# AVR_PCB.net
KiCad netlist of a schematic drawn in Altium Designer
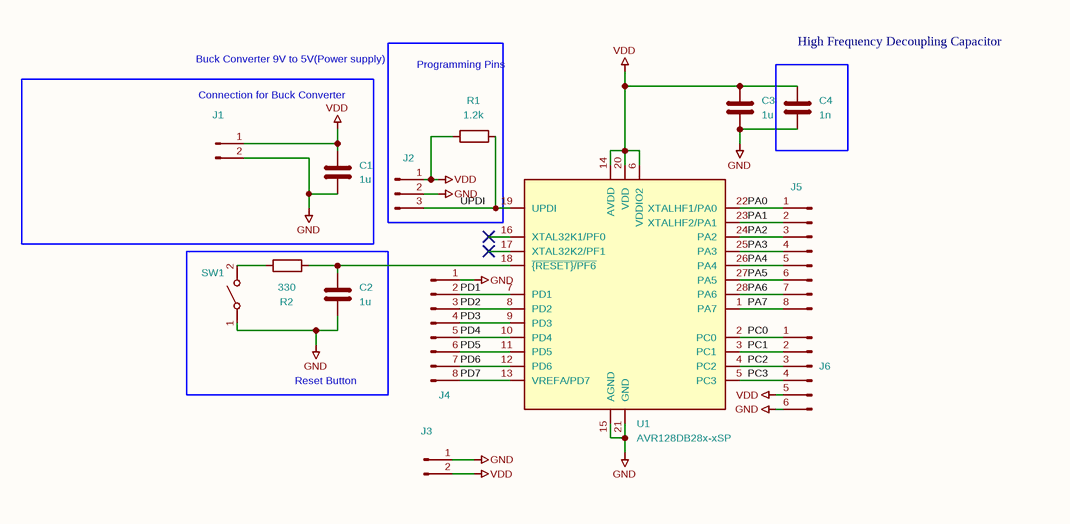
[diagram p0: AVR PCB.SchDoc]

(export (version "E")
  (design (tool "Eeschema 10.0.6"))
  (components
    (comp (ref "C1")
      (value "1u")
      (footprint "C_Disc_D7.5mm_W2.5mm_P5.00mm")
      (libsource (lib "Device") (part "C"))
    )
    (comp (ref "C2")
      (value "1u")
      (footprint "C_Disc_D7.5mm_W2.5mm_P5.00mm")
      (libsource (lib "Device") (part "C"))
    )
    (comp (ref "C3")
      (value "1u")
      (footprint "C_Disc_D7.5mm_W2.5mm_P5.00mm")
      (libsource (lib "Device") (part "C"))
    )
    (comp (ref "C4")
      (value "1n")
      (footprint "C_Disc_D7.5mm_W2.5mm_P5.00mm")
      (libsource (lib "Device") (part "C"))
    )
    (comp (ref "J1")
      (value "Conn_01x02_Pin")
      (footprint "PinHeader_1x02_P2.54mm_Vertical")
      (libsource (lib "Connector") (part "Conn_01x02_Pin"))
    )
    (comp (ref "J2")
      (value "Conn_01x03_Male")
      (footprint "PinHeader_1x03_P2.54mm_Vertical")
      (libsource (lib "Connector") (part "Conn_01x03_Male"))
    )
    (comp (ref "J3")
      (value "Conn_01x02_Male")
      (footprint "PinHeader_1x02_P2.54mm_Vertical")
      (libsource (lib "Connector") (part "Conn_01x02_Male"))
    )
    (comp (ref "J4")
      (value "Conn_01x08_Male")
      (footprint "PinHeader_1x08_P2.54mm_Vertical")
      (libsource (lib "Connector") (part "Conn_01x08_Male"))
    )
    (comp (ref "J5")
      (value "Conn_01x08_Male")
      (footprint "PinHeader_1x08_P2.54mm_Vertical")
      (libsource (lib "") (part "Conn_01x08_Male_1"))
    )
    (comp (ref "J6")
      (value "Conn_01x06_Male")
      (footprint "PinHeader_1x06_P2.54mm_Vertical")
      (libsource (lib "Connector") (part "Conn_01x06_Male"))
    )
    (comp (ref "R1")
      (value "1.2k")
      (footprint "R_Axial_DIN0309_L9.0mm_D3.2mm_P12.70mm_Horizontal")
      (libsource (lib "Device") (part "R"))
    )
    (comp (ref "R2")
      (value "330")
      (footprint "R_Axial_DIN0309_L9.0mm_D3.2mm_P12.70mm_Horizontal")
      (libsource (lib "") (part "R_1"))
    )
    (comp (ref "SW1") (value "SW_SPST") (footprint "SW_PUSH_6mm") (libsource (lib "Switch") (part "SW_SPST")))
    (comp (ref "U1")
      (value "AVR128DB28x-xSP")
      (footprint "DIP-28_W7.62mm")
      (libsource (lib "MCU_Microchip_AVR_Dx") (part "AVR128DB28x-xSP"))
    )
  )
  (nets
    (net (code "1") (name "/PA0") (class "Default")
      (node (ref "J5") (pin "1") (pinfunction "Pin_1_1") (pintype "passive"))
      (node (ref "U1") (pin "22") (pinfunction "XTALHF1/PA0_22") (pintype "passive"))
    )
    (net (code "2") (name "/PA1") (class "Default")
      (node (ref "J5") (pin "2") (pinfunction "Pin_2_2") (pintype "passive"))
      (node (ref "U1") (pin "23") (pinfunction "XTALHF2/PA1_23") (pintype "passive"))
    )
    (net (code "3") (name "/PA2") (class "Default")
      (node (ref "J5") (pin "3") (pinfunction "Pin_3_3") (pintype "passive"))
      (node (ref "U1") (pin "24") (pinfunction "PA2_24") (pintype "passive"))
    )
    (net (code "4") (name "/PA3") (class "Default")
      (node (ref "J5") (pin "4") (pinfunction "Pin_4_4") (pintype "passive"))
      (node (ref "U1") (pin "25") (pinfunction "PA3_25") (pintype "passive"))
    )
    (net (code "5") (name "/PA4") (class "Default")
      (node (ref "J5") (pin "5") (pinfunction "Pin_5_5") (pintype "passive"))
      (node (ref "U1") (pin "26") (pinfunction "PA4_26") (pintype "passive"))
    )
    (net (code "6") (name "/PA5") (class "Default")
      (node (ref "J5") (pin "6") (pinfunction "Pin_6_6") (pintype "passive"))
      (node (ref "U1") (pin "27") (pinfunction "PA5_27") (pintype "passive"))
    )
    (net (code "7") (name "/PA6") (class "Default")
      (node (ref "J5") (pin "7") (pinfunction "Pin_7_7") (pintype "passive"))
      (node (ref "U1") (pin "28") (pinfunction "PA6_28") (pintype "passive"))
    )
    (net (code "8") (name "/PA7") (class "Default")
      (node (ref "J5") (pin "8") (pinfunction "Pin_8_8") (pintype "passive"))
      (node (ref "U1") (pin "1") (pinfunction "PA7_1") (pintype "passive"))
    )
    (net (code "9") (name "/PC0") (class "Default")
      (node (ref "J6") (pin "1") (pinfunction "Pin_1_1") (pintype "passive"))
      (node (ref "U1") (pin "2") (pinfunction "PC0_2") (pintype "passive"))
    )
    (net (code "10") (name "/PC1") (class "Default")
      (node (ref "J6") (pin "2") (pinfunction "Pin_2_2") (pintype "passive"))
      (node (ref "U1") (pin "3") (pinfunction "PC1_3") (pintype "passive"))
    )
    (net (code "11") (name "/PC2") (class "Default")
      (node (ref "J6") (pin "3") (pinfunction "Pin_3_3") (pintype "passive"))
      (node (ref "U1") (pin "4") (pinfunction "PC2_4") (pintype "passive"))
    )
    (net (code "12") (name "/PC3") (class "Default")
      (node (ref "J6") (pin "4") (pinfunction "Pin_4_4") (pintype "passive"))
      (node (ref "U1") (pin "5") (pinfunction "PC3_5") (pintype "passive"))
    )
    (net (code "13") (name "/PD1") (class "Default")
      (node (ref "J4") (pin "2") (pinfunction "Pin_2_2") (pintype "passive"))
      (node (ref "U1") (pin "7") (pinfunction "PD1_7") (pintype "passive"))
    )
    (net (code "14") (name "/PD2") (class "Default")
      (node (ref "J4") (pin "3") (pinfunction "Pin_3_3") (pintype "passive"))
      (node (ref "U1") (pin "8") (pinfunction "PD2_8") (pintype "passive"))
    )
    (net (code "15") (name "/PD3") (class "Default")
      (node (ref "J4") (pin "4") (pinfunction "Pin_4_4") (pintype "passive"))
      (node (ref "U1") (pin "9") (pinfunction "PD3_9") (pintype "passive"))
    )
    (net (code "16") (name "/PD4") (class "Default")
      (node (ref "J4") (pin "5") (pinfunction "Pin_5_5") (pintype "passive"))
      (node (ref "U1") (pin "10") (pinfunction "PD4_10") (pintype "passive"))
    )
    (net (code "17") (name "/PD5") (class "Default")
      (node (ref "J4") (pin "6") (pinfunction "Pin_6_6") (pintype "passive"))
      (node (ref "U1") (pin "11") (pinfunction "PD5_11") (pintype "passive"))
    )
    (net (code "18") (name "/PD6") (class "Default")
      (node (ref "J4") (pin "7") (pinfunction "Pin_7_7") (pintype "passive"))
      (node (ref "U1") (pin "12") (pinfunction "PD6_12") (pintype "passive"))
    )
    (net (code "19") (name "/PD7") (class "Default")
      (node (ref "J4") (pin "8") (pinfunction "Pin_8_8") (pintype "passive"))
      (node (ref "U1") (pin "13") (pinfunction "VREFA/PD7_13") (pintype "passive"))
    )
    (net (code "20") (name "/UPDI") (class "Default")
      (node (ref "J2") (pin "3") (pinfunction "Pin_3_3") (pintype "passive"))
      (node (ref "R1") (pin "2") (pinfunction "2_2") (pintype "passive"))
      (node (ref "U1") (pin "19") (pinfunction "UPDI_19") (pintype "passive"))
    )
    (net (code "21") (name "GND") (class "Default")
      (node (ref "C1") (pin "2") (pinfunction "2_2") (pintype "passive"))
      (node (ref "C2") (pin "2") (pinfunction "2_2") (pintype "passive"))
      (node (ref "C3") (pin "2") (pinfunction "2_2") (pintype "passive"))
      (node (ref "C4") (pin "2") (pinfunction "2_2") (pintype "passive"))
      (node (ref "J1") (pin "2") (pinfunction "Pin_2_2") (pintype "passive"))
      (node (ref "J2") (pin "2") (pinfunction "Pin_2_2") (pintype "passive"))
      (node (ref "J3") (pin "1") (pinfunction "Pin_1_1") (pintype "passive"))
      (node (ref "J4") (pin "1") (pinfunction "Pin_1_1") (pintype "passive"))
      (node (ref "J6") (pin "6") (pinfunction "Pin_6_6") (pintype "passive"))
      (node (ref "SW1") (pin "1") (pinfunction "A_1") (pintype "passive"))
      (node (ref "U1") (pin "15") (pinfunction "AGND_15") (pintype "passive"))
      (node (ref "U1") (pin "21") (pinfunction "GND_21") (pintype "passive"))
    )
    (net (code "22") (name "Net-(SW1-B)") (class "Default")
      (node (ref "R2") (pin "1") (pinfunction "1_1") (pintype "passive"))
      (node (ref "SW1") (pin "2") (pinfunction "B_2") (pintype "passive"))
    )
    (net (code "23") (name "Net-(U1-~{{RESET}{slash}PF6})") (class "Default")
      (node (ref "C2") (pin "1") (pinfunction "1_1") (pintype "passive"))
      (node (ref "R2") (pin "2") (pinfunction "2_2") (pintype "passive"))
      (node (ref "U1") (pin "18") (pinfunction "~{{RESET}/PF6}_18") (pintype "passive"))
    )
    (net (code "24") (name "VDD") (class "Default")
      (node (ref "C1") (pin "1") (pinfunction "1_1") (pintype "passive"))
      (node (ref "C3") (pin "1") (pinfunction "1_1") (pintype "passive"))
      (node (ref "C4") (pin "1") (pinfunction "1_1") (pintype "passive"))
      (node (ref "J1") (pin "1") (pinfunction "Pin_1_1") (pintype "passive"))
      (node (ref "J2") (pin "1") (pinfunction "Pin_1_1") (pintype "passive"))
      (node (ref "J3") (pin "2") (pinfunction "Pin_2_2") (pintype "passive"))
      (node (ref "J6") (pin "5") (pinfunction "Pin_5_5") (pintype "passive"))
      (node (ref "R1") (pin "1") (pinfunction "1_1") (pintype "passive"))
      (node (ref "U1") (pin "14") (pinfunction "AVDD_14") (pintype "passive"))
      (node (ref "U1") (pin "20") (pinfunction "VDD_20") (pintype "passive"))
      (node (ref "U1") (pin "6") (pinfunction "VDDIO2_6") (pintype "passive"))
    )
    (net (code "25") (name "unconnected-(U1-XTAL32K1{slash}PF0-Pad16)") (class "Default")
      (node (ref "U1") (pin "16") (pinfunction "XTAL32K1/PF0_16") (pintype "passive+no_connect"))
    )
    (net (code "26") (name "unconnected-(U1-XTAL32K2{slash}PF1-Pad17)") (class "Default")
      (node (ref "U1") (pin "17") (pinfunction "XTAL32K2/PF1_17") (pintype "passive+no_connect"))
    )
  )
)
